# LampBoxV0_31-THT.net
KiCad netlist of a schematic drawn in EAGLE
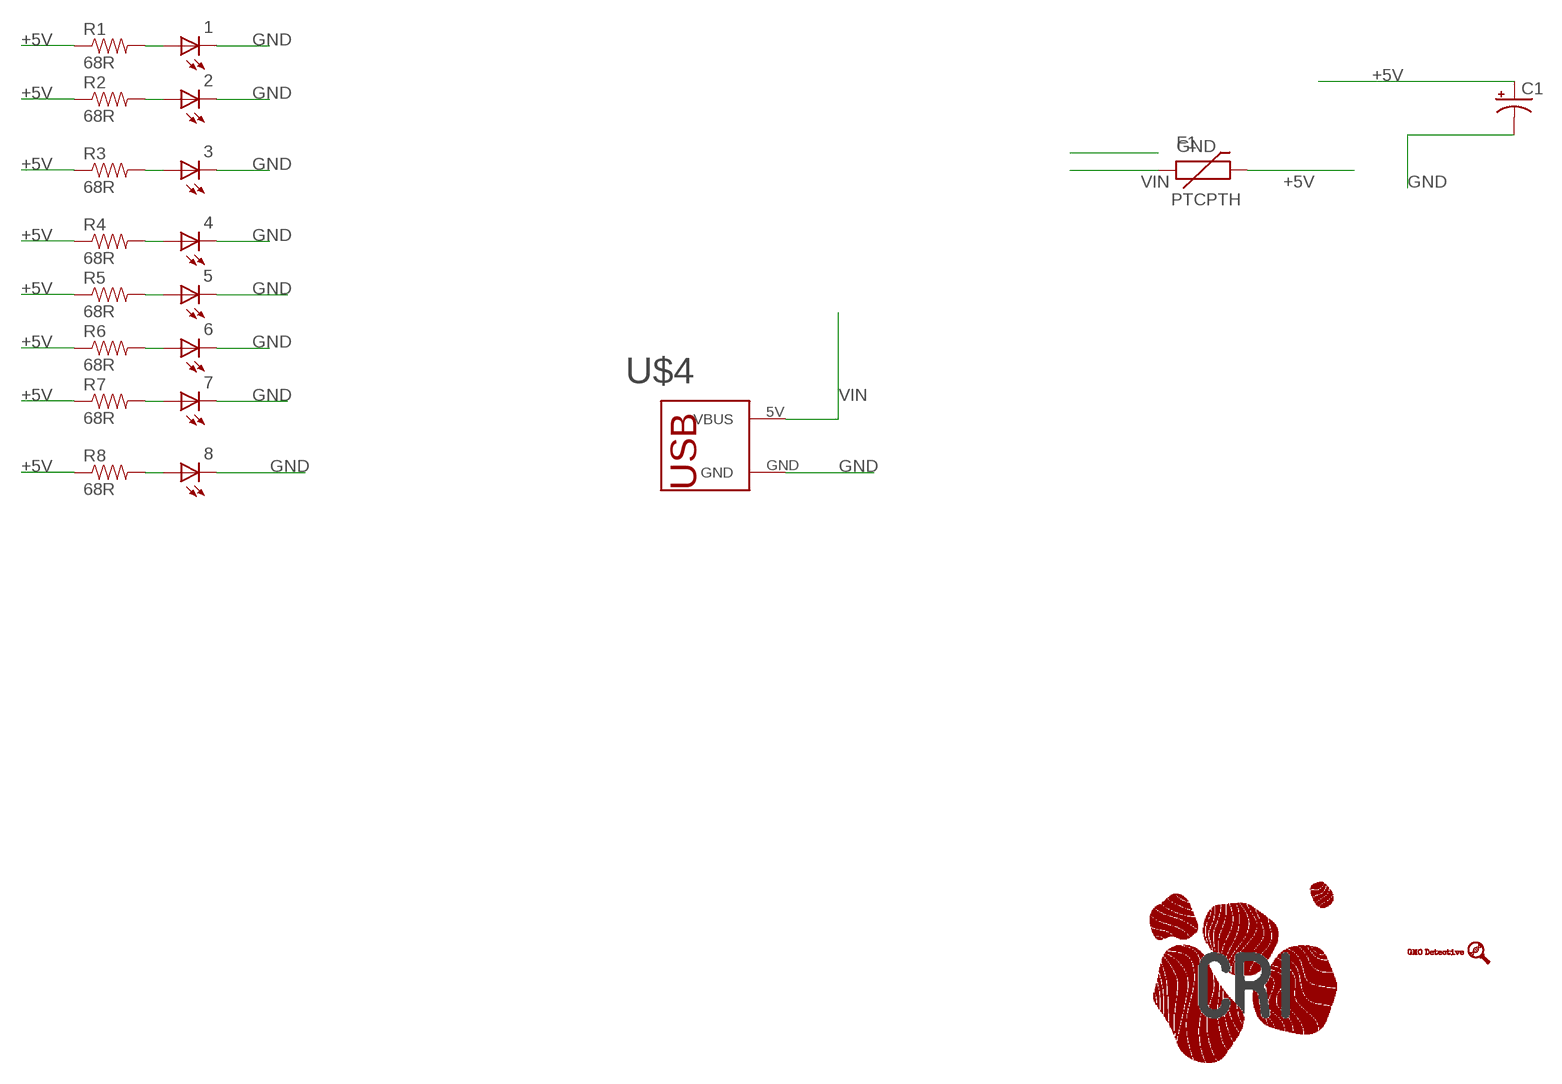
[diagram p0: schematic, sheet 1]

(export (version "E")
  (design (tool "Eeschema 10.0.6"))
  (components
    (comp (ref "1")
      (value "LEDGMODETECTOR")
      (footprint "eagle-import:LED_5MM")
      (fields (field (name "MPN") " C503B-BAN-CZ0A0451"))
      (libsource (lib "eagle-import") (part "LEDGMODETECTOR"))
    )
    (comp (ref "2")
      (value "LEDGMODETECTOR")
      (footprint "eagle-import:LED_5MM")
      (fields (field (name "MPN") " C503B-BAN-CZ0A0451"))
      (libsource (lib "eagle-import") (part "LEDGMODETECTOR"))
    )
    (comp (ref "3")
      (value "LEDGMODETECTOR")
      (footprint "eagle-import:LED_5MM")
      (fields (field (name "MPN") " C503B-BAN-CZ0A0451"))
      (libsource (lib "eagle-import") (part "LEDGMODETECTOR"))
    )
    (comp (ref "4")
      (value "LEDGMODETECTOR")
      (footprint "eagle-import:LED_5MM")
      (fields (field (name "MPN") " C503B-BAN-CZ0A0451"))
      (libsource (lib "eagle-import") (part "LEDGMODETECTOR"))
    )
    (comp (ref "5")
      (value "LEDGMODETECTOR")
      (footprint "eagle-import:LED_5MM")
      (fields (field (name "MPN") " C503B-BAN-CZ0A0451"))
      (libsource (lib "eagle-import") (part "LEDGMODETECTOR"))
    )
    (comp (ref "6")
      (value "LEDGMODETECTOR")
      (footprint "eagle-import:LED_5MM")
      (fields (field (name "MPN") " C503B-BAN-CZ0A0451"))
      (libsource (lib "eagle-import") (part "LEDGMODETECTOR"))
    )
    (comp (ref "7")
      (value "LEDGMODETECTOR")
      (footprint "eagle-import:LED_5MM")
      (fields (field (name "MPN") " C503B-BAN-CZ0A0451"))
      (libsource (lib "eagle-import") (part "LEDGMODETECTOR"))
    )
    (comp (ref "8")
      (value "LEDGMODETECTOR")
      (footprint "eagle-import:LED_5MM")
      (fields (field (name "MPN") " C503B-BAN-CZ0A0451"))
      (libsource (lib "eagle-import") (part "LEDGMODETECTOR"))
    )
    (comp (ref "C1")
      (value "10UF-POLARGMODETECTOR")
      (footprint "eagle-import:CPOL-RADIAL-2.5MM-5MM")
      (fields (field (name "MPN") "ECA-1JM100B"))
      (libsource (lib "eagle-import") (part "10UF-POLARGMODETECTOR"))
    )
    (comp (ref "F1")
      (value "PTCPTH")
      (footprint "eagle-import:PTC")
      (libsource (lib "eagle-import") (part "PTCPTH"))
    )
    (comp (ref "R1")
      (value "68R")
      (footprint "eagle-import:AXIAL-0.3")
      (libsource (lib "eagle-import") (part "RESISTORAXIAL-0.3"))
    )
    (comp (ref "R2")
      (value "68R")
      (footprint "eagle-import:AXIAL-0.3")
      (libsource (lib "eagle-import") (part "RESISTORAXIAL-0.3"))
    )
    (comp (ref "R3")
      (value "68R")
      (footprint "eagle-import:AXIAL-0.3")
      (libsource (lib "eagle-import") (part "RESISTORAXIAL-0.3"))
    )
    (comp (ref "R4")
      (value "68R")
      (footprint "eagle-import:AXIAL-0.3")
      (libsource (lib "eagle-import") (part "RESISTORAXIAL-0.3"))
    )
    (comp (ref "R5")
      (value "68R")
      (footprint "eagle-import:AXIAL-0.3")
      (libsource (lib "eagle-import") (part "RESISTORAXIAL-0.3"))
    )
    (comp (ref "R6")
      (value "68R")
      (footprint "eagle-import:AXIAL-0.3")
      (libsource (lib "eagle-import") (part "RESISTORAXIAL-0.3"))
    )
    (comp (ref "R7")
      (value "68R")
      (footprint "eagle-import:AXIAL-0.3")
      (libsource (lib "eagle-import") (part "RESISTORAXIAL-0.3"))
    )
    (comp (ref "R8")
      (value "68R")
      (footprint "eagle-import:AXIAL-0.3")
      (libsource (lib "eagle-import") (part "RESISTORAXIAL-0.3"))
    )
    (comp (ref "U$2")
      (value "LOGO_GMO_DETECTIVENEW")
      (footprint "eagle-import:LOGO_GMO_DETECTIVE")
      (libsource (lib "eagle-import") (part "LOGO_GMO_DETECTIVENEW"))
    )
    (comp (ref "U$3")
      (value "LOGO-CRI-NEW-110MM-BOTTOM-SILK")
      (footprint "eagle-import:LOGO_CRI-NEW-BMP10MM-BOTTOM")
      (libsource (lib "eagle-import") (part "LOGO-CRI-NEW-110MM-BOTTOM-SILK"))
    )
    (comp (ref "U$4")
      (value "USB-2P")
      (footprint "eagle-import:MICRO-USB2P-TB1")
      (libsource (lib "eagle-import") (part "USB-2P"))
    )
  )
  (nets
    (net (code "1") (name "/+5V") (class "Default")
      (node (ref "C1") (pin "1") (pinfunction "+_1") (pintype "passive"))
      (node (ref "F1") (pin "P$2") (pinfunction "2_P$2") (pintype "bidirectional"))
      (node (ref "R1") (pin "P$1") (pinfunction "1_P$1") (pintype "passive"))
      (node (ref "R2") (pin "P$1") (pinfunction "1_P$1") (pintype "passive"))
      (node (ref "R3") (pin "P$1") (pinfunction "1_P$1") (pintype "passive"))
      (node (ref "R4") (pin "P$1") (pinfunction "1_P$1") (pintype "passive"))
      (node (ref "R5") (pin "P$1") (pinfunction "1_P$1") (pintype "passive"))
      (node (ref "R6") (pin "P$1") (pinfunction "1_P$1") (pintype "passive"))
      (node (ref "R7") (pin "P$1") (pinfunction "1_P$1") (pintype "passive"))
      (node (ref "R8") (pin "P$1") (pinfunction "1_P$1") (pintype "passive"))
    )
    (net (code "2") (name "/GND") (class "Default")
      (node (ref "1") (pin "K") (pinfunction "C_K") (pintype "passive"))
      (node (ref "2") (pin "K") (pinfunction "C_K") (pintype "passive"))
      (node (ref "3") (pin "K") (pinfunction "C_K") (pintype "passive"))
      (node (ref "4") (pin "K") (pinfunction "C_K") (pintype "passive"))
      (node (ref "5") (pin "K") (pinfunction "C_K") (pintype "passive"))
      (node (ref "6") (pin "K") (pinfunction "C_K") (pintype "passive"))
      (node (ref "7") (pin "K") (pinfunction "C_K") (pintype "passive"))
      (node (ref "8") (pin "K") (pinfunction "C_K") (pintype "passive"))
      (node (ref "C1") (pin "2") (pinfunction "-_2") (pintype "passive"))
      (node (ref "U$4") (pin "GND") (pinfunction "GND_GND") (pintype "bidirectional"))
    )
    (net (code "3") (name "/VIN") (class "Default")
      (node (ref "F1") (pin "P$1") (pinfunction "1_P$1") (pintype "bidirectional"))
      (node (ref "U$4") (pin "5V") (pinfunction "VBUS_5V") (pintype "bidirectional"))
    )
    (net (code "4") (name "Net-(R1-2)") (class "Default")
      (node (ref "1") (pin "A") (pinfunction "A_A") (pintype "passive"))
      (node (ref "R1") (pin "P$2") (pinfunction "2_P$2") (pintype "passive"))
    )
    (net (code "5") (name "Net-(R2-2)") (class "Default")
      (node (ref "2") (pin "A") (pinfunction "A_A") (pintype "passive"))
      (node (ref "R2") (pin "P$2") (pinfunction "2_P$2") (pintype "passive"))
    )
    (net (code "6") (name "Net-(R3-2)") (class "Default")
      (node (ref "3") (pin "A") (pinfunction "A_A") (pintype "passive"))
      (node (ref "R3") (pin "P$2") (pinfunction "2_P$2") (pintype "passive"))
    )
    (net (code "7") (name "Net-(R4-2)") (class "Default")
      (node (ref "4") (pin "A") (pinfunction "A_A") (pintype "passive"))
      (node (ref "R4") (pin "P$2") (pinfunction "2_P$2") (pintype "passive"))
    )
    (net (code "8") (name "Net-(R5-2)") (class "Default")
      (node (ref "5") (pin "A") (pinfunction "A_A") (pintype "passive"))
      (node (ref "R5") (pin "P$2") (pinfunction "2_P$2") (pintype "passive"))
    )
    (net (code "9") (name "Net-(R6-2)") (class "Default")
      (node (ref "6") (pin "A") (pinfunction "A_A") (pintype "passive"))
      (node (ref "R6") (pin "P$2") (pinfunction "2_P$2") (pintype "passive"))
    )
    (net (code "10") (name "Net-(R7-2)") (class "Default")
      (node (ref "7") (pin "A") (pinfunction "A_A") (pintype "passive"))
      (node (ref "R7") (pin "P$2") (pinfunction "2_P$2") (pintype "passive"))
    )
    (net (code "11") (name "Net-(R8-2)") (class "Default")
      (node (ref "8") (pin "A") (pinfunction "A_A") (pintype "passive"))
      (node (ref "R8") (pin "P$2") (pinfunction "2_P$2") (pintype "passive"))
    )
  )
)
